# BodyCaINv0_1.net
KiCad netlist of a schematic drawn in Altium Designer
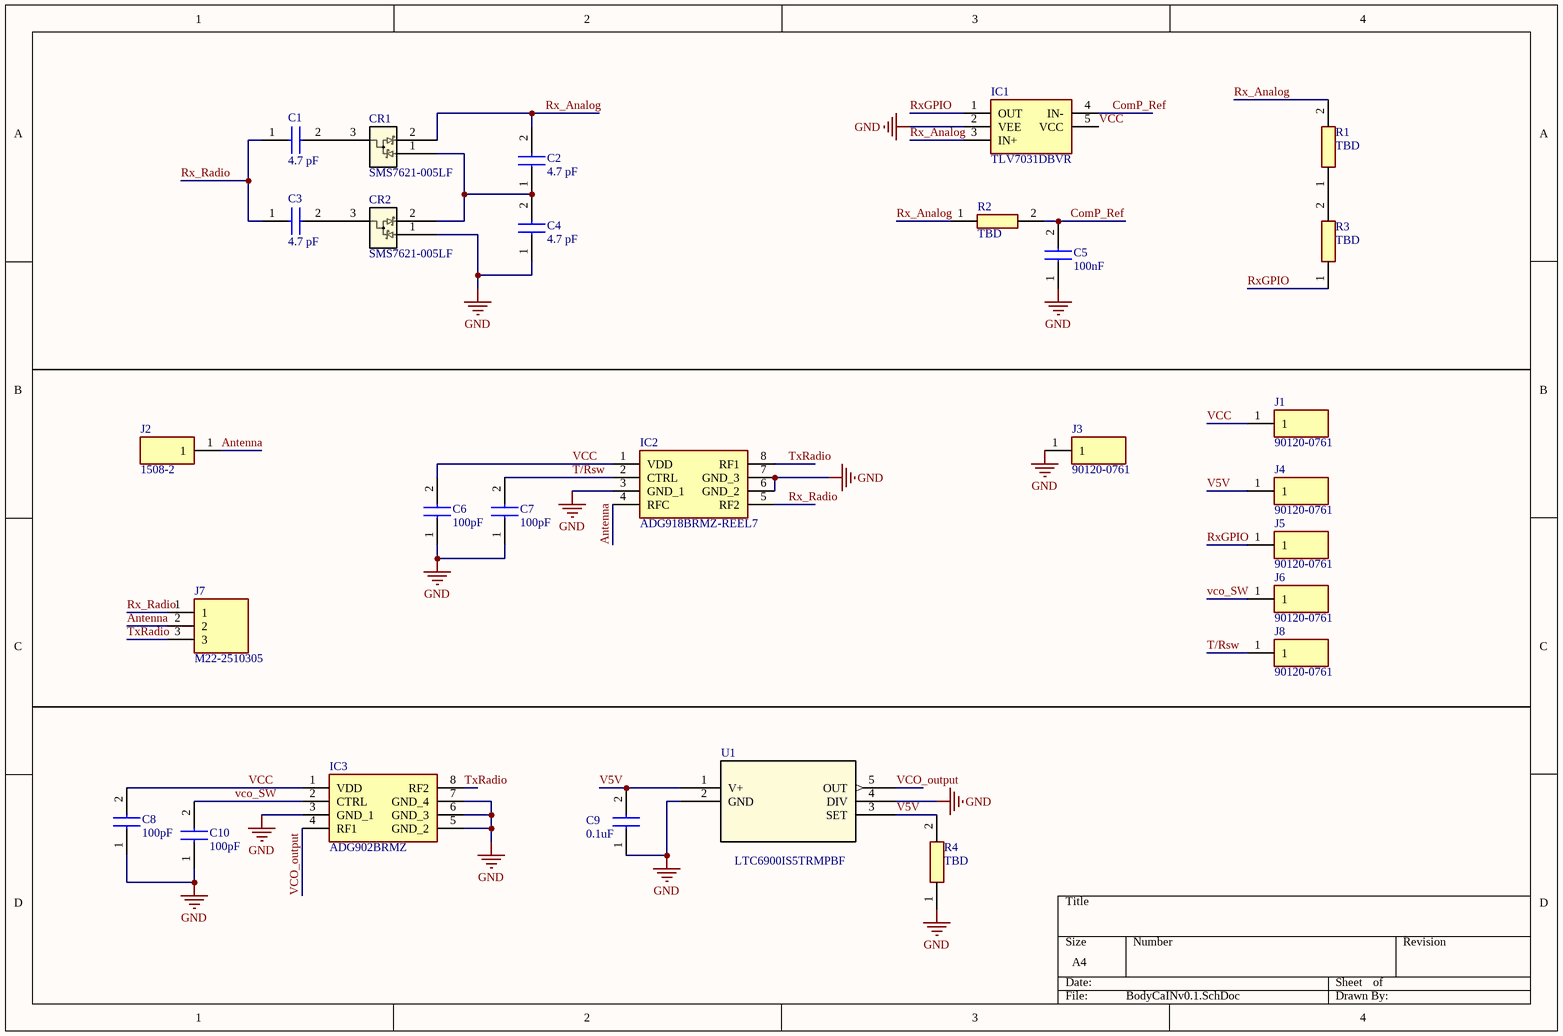
[diagram p0: BodyCaINv0.1.SchDoc]

(export (version "E")
  (design (tool "Eeschema 10.0.6"))
  (components
    (comp (ref "C1")
      (value "4.7 pF")
      (footprint "SamacSys:CAPC1608X73N")
      (description "Capacitor 06035J4R7BBSTR")
      (fields
        (field (name "MANUFACTURER_PART_NUMBER") "06035J4R7BBSTR")
        (field (name "MOUSER PART NUMBER") "581-06035J4R7BBS")
      )
      (libsource (lib "*") (part "06035J4R7BBSTR"))
    )
    (comp (ref "C2")
      (value "4.7 pF")
      (footprint "SamacSys:CAPC1608X73N")
      (description "Capacitor 06035J4R7BBSTR")
      (fields
        (field (name "MANUFACTURER_PART_NUMBER") "06035J4R7BBSTR")
        (field (name "MOUSER PART NUMBER") "581-06035J4R7BBS")
      )
      (libsource (lib "*") (part "06035J4R7BBSTR"))
    )
    (comp (ref "C3")
      (value "4.7 pF")
      (footprint "SamacSys:CAPC1608X73N")
      (description "Capacitor 06035J4R7BBSTR")
      (fields
        (field (name "MANUFACTURER_PART_NUMBER") "06035J4R7BBSTR")
        (field (name "MOUSER PART NUMBER") "581-06035J4R7BBS")
      )
      (libsource (lib "*") (part "06035J4R7BBSTR"))
    )
    (comp (ref "C4")
      (value "4.7 pF")
      (footprint "SamacSys:CAPC1608X73N")
      (description "Capacitor 06035J4R7BBSTR")
      (fields
        (field (name "MANUFACTURER_PART_NUMBER") "06035J4R7BBSTR")
        (field (name "MOUSER PART NUMBER") "581-06035J4R7BBS")
      )
      (libsource (lib "*") (part "06035J4R7BBSTR"))
    )
    (comp (ref "C5")
      (value "100nF")
      (footprint "SamacSys:CAPC1608X90N")
      (description "Capacitor GCM188R71H103KA37J")
      (fields
        (field (name "MANUFACTURER_PART_NUMBER") "GCM188R71H103KA37J")
        (field (name "MOUSER PART NUMBER") "81-GCM188R71H103KA7J")
      )
      (libsource (lib "*") (part "GCM188R71H103KA37J"))
    )
    (comp (ref "C6")
      (value "100pF")
      (footprint "SamacSys:CAPC1608X97N")
      (description "Capacitor VJ0603A101FXAAC")
      (fields
        (field (name "MANUFACTURER_PART_NUMBER") "VJ0603A101FXAAC")
        (field (name "MOUSER PART NUMBER") "77-VJ0603A101FXAAC")
      )
      (libsource (lib "*") (part "VJ0603A101FXAAC"))
    )
    (comp (ref "C7")
      (value "100pF")
      (footprint "SamacSys:CAPC1608X97N")
      (description "Capacitor VJ0603A101FXAAC")
      (fields
        (field (name "MANUFACTURER_PART_NUMBER") "VJ0603A101FXAAC")
        (field (name "MOUSER PART NUMBER") "77-VJ0603A101FXAAC")
      )
      (libsource (lib "*") (part "VJ0603A101FXAAC"))
    )
    (comp (ref "C8")
      (value "100pF")
      (footprint "SamacSys:CAPC1608X97N")
      (description "Capacitor VJ0603A101FXAAC")
      (fields
        (field (name "MANUFACTURER_PART_NUMBER") "VJ0603A101FXAAC")
        (field (name "MOUSER PART NUMBER") "77-VJ0603A101FXAAC")
      )
      (libsource (lib "*") (part "VJ0603A101FXAAC"))
    )
    (comp (ref "C9")
      (value "0.1uF")
      (footprint "SamacSys:CAPC1608X100N")
      (description "CapacitorC0603X104K1RACTU")
      (fields (field (name "MANUFACTURER_PART_NUMBER") "C0603X104K1RACTU"))
      (libsource (lib "*") (part "C0603X104K1RACTU"))
    )
    (comp (ref "C10")
      (value "100pF")
      (footprint "SamacSys:CAPC1608X97N")
      (description "Capacitor VJ0603A101FXAAC")
      (fields
        (field (name "MANUFACTURER_PART_NUMBER") "VJ0603A101FXAAC")
        (field (name "MOUSER PART NUMBER") "77-VJ0603A101FXAAC")
      )
      (libsource (lib "*") (part "VJ0603A101FXAAC"))
    )
    (comp (ref "CR1")
      (value "SMS7621-005LF")
      (footprint "SOT23")
      (description "No Description Available")
      (libsource (lib "SMS7621-005LF") (part "SMS7621-005LF"))
    )
    (comp (ref "CR2")
      (value "SMS7621-005LF")
      (footprint "SOT23")
      (description "No Description Available")
      (libsource (lib "SMS7621-005LF") (part "SMS7621-005LF"))
    )
    (comp (ref "IC1")
      (value "TLV7031DBVR")
      (footprint "SOT95P280X145-5N")
      (description "Integrated Circuit")
      (fields (field (name "MOUSER PART NUMBER") "595-TLV7031DBVR"))
      (libsource (lib "CaINv3.02") (part "TLV7031DBVR"))
    )
    (comp (ref "IC2")
      (value "ADG918BRMZ-REEL7")
      (footprint "SOP65P490X110-8N")
      (description "Integrated Circuit")
      (fields (field (name "MOUSER PART NUMBER") "584-ADG918BRMZ-R7"))
      (libsource (lib "CaINv3.02") (part "ADG918BRMZ-REEL7"))
    )
    (comp (ref "IC3")
      (value "ADG902BRMZ")
      (footprint "SOP65P490X110-8N")
      (description "Integrated Circuit")
      (fields (field (name "MOUSER PART NUMBER") "584-ADG902BRMZ"))
      (libsource (lib "CaINv3.02") (part "ADG902BRMZ"))
    )
    (comp (ref "J1")
      (value "90120-0761")
      (footprint "SamacSys:HDRV1W90P0X254_1X1_232X249X560P")
      (description "Connector")
      (fields (field (name "MOUSER PART NUMBER") "538-90120-0761"))
      (libsource (lib "*") (part "90120-0761"))
    )
    (comp (ref "J2")
      (value "1508-2")
      (footprint "SamacSys:15082")
      (description "Connector")
      (fields (field (name "MOUSER PART NUMBER") "534-1508-2"))
      (libsource (lib "*") (part "1508-2"))
    )
    (comp (ref "J3")
      (value "90120-0761")
      (footprint "SamacSys:HDRV1W90P0X254_1X1_232X249X560P")
      (description "Connector")
      (fields (field (name "MOUSER PART NUMBER") "538-90120-0761"))
      (libsource (lib "*") (part "90120-0761"))
    )
    (comp (ref "J4")
      (value "90120-0761")
      (footprint "SamacSys:HDRV1W90P0X254_1X1_232X249X560P")
      (description "Connector")
      (fields (field (name "MOUSER PART NUMBER") "538-90120-0761"))
      (libsource (lib "*") (part "90120-0761"))
    )
    (comp (ref "J5")
      (value "90120-0761")
      (footprint "SamacSys:HDRV1W90P0X254_1X1_232X249X560P")
      (description "Connector")
      (fields (field (name "MOUSER PART NUMBER") "538-90120-0761"))
      (libsource (lib "*") (part "90120-0761"))
    )
    (comp (ref "J6")
      (value "90120-0761")
      (footprint "SamacSys:HDRV1W90P0X254_1X1_232X249X560P")
      (description "Connector")
      (fields (field (name "MOUSER PART NUMBER") "538-90120-0761"))
      (libsource (lib "*") (part "90120-0761"))
    )
    (comp (ref "J7")
      (value "M22-2510305")
      (footprint "HDRV3W60P0X200_1X3_600X200X525P")
      (description "Connector")
      (fields (field (name "MOUSER PART NUMBER") "855-M22-2510305"))
      (libsource (lib "CaINv3.02") (part "M22-2510305"))
    )
    (comp (ref "J8")
      (value "90120-0761")
      (footprint "SamacSys:HDRV1W90P0X254_1X1_232X249X560P")
      (description "Connector")
      (fields (field (name "MOUSER PART NUMBER") "538-90120-0761"))
      (libsource (lib "*") (part "90120-0761"))
    )
    (comp (ref "R1")
      (value "TBD")
      (footprint "SamacSys:RESC1508X46N")
      (description "Resistor WSL060300000ZEA9")
      (fields
        (field (name "MANUFACTURER_PART_NUMBER") "WSL060300000ZEA9")
        (field (name "MOUSER PART NUMBER") "71-WSL060300000ZEA9")
      )
      (libsource (lib "") (part "WSL060300000ZEA9_1"))
    )
    (comp (ref "R2")
      (value "TBD")
      (footprint "SamacSys:RESC1508X46N")
      (description "Resistor WSL060300000ZEA9")
      (fields
        (field (name "MANUFACTURER_PART_NUMBER") "WSL060300000ZEA9")
        (field (name "MOUSER PART NUMBER") "71-WSL060300000ZEA9")
      )
      (libsource (lib "*") (part "WSL060300000ZEA9"))
    )
    (comp (ref "R3")
      (value "TBD")
      (footprint "SamacSys:RESC1508X46N")
      (description "Resistor WSL060300000ZEA9")
      (fields
        (field (name "MANUFACTURER_PART_NUMBER") "WSL060300000ZEA9")
        (field (name "MOUSER PART NUMBER") "71-WSL060300000ZEA9")
      )
      (libsource (lib "") (part "WSL060300000ZEA9_1"))
    )
    (comp (ref "R4")
      (value "TBD")
      (footprint "SamacSys:RESC1508X46N")
      (description "Resistor WSL060300000ZEA9")
      (fields
        (field (name "MANUFACTURER_PART_NUMBER") "WSL060300000ZEA9")
        (field (name "MOUSER PART NUMBER") "71-WSL060300000ZEA9")
      )
      (libsource (lib "") (part "WSL060300000ZEA9_1"))
    )
    (comp (ref "U1")
      (value "LTC6900IS5TRMPBF")
      (footprint "S_5_ADI")
      (description "No Description Available")
      (libsource (lib "LTC6900IS5TRMPBF") (part "LTC6900IS5TRMPBF"))
    )
  )
  (nets
    (net (code "1") (name "/Antenna") (class "Default")
      (node (ref "IC2") (pin "4") (pinfunction "RFC_4") (pintype "passive"))
      (node (ref "J2") (pin "1") (pinfunction "1_1") (pintype "passive"))
      (node (ref "J7") (pin "2") (pinfunction "2_2") (pintype "passive"))
    )
    (net (code "2") (name "/ComP_Ref") (class "Default")
      (node (ref "C5") (pin "2") (pinfunction "2_2") (pintype "passive"))
      (node (ref "IC1") (pin "4") (pinfunction "IN-_4") (pintype "passive"))
      (node (ref "R2") (pin "2") (pinfunction "2_2") (pintype "passive"))
    )
    (net (code "3") (name "/RxGPIO") (class "Default")
      (node (ref "IC1") (pin "1") (pinfunction "OUT_1") (pintype "passive"))
      (node (ref "J5") (pin "1") (pinfunction "1_1") (pintype "passive"))
      (node (ref "R3") (pin "1") (pinfunction "1_1") (pintype "passive"))
    )
    (net (code "4") (name "/Rx_Analog") (class "Default")
      (node (ref "C2") (pin "2") (pinfunction "2_2") (pintype "passive"))
      (node (ref "CR1") (pin "2") (pinfunction "2_2") (pintype "passive"))
      (node (ref "IC1") (pin "3") (pinfunction "IN+_3") (pintype "passive"))
      (node (ref "R1") (pin "2") (pinfunction "2_2") (pintype "passive"))
      (node (ref "R2") (pin "1") (pinfunction "1_1") (pintype "passive"))
    )
    (net (code "5") (name "/Rx_Radio") (class "Default")
      (node (ref "C1") (pin "1") (pinfunction "1_1") (pintype "passive"))
      (node (ref "C3") (pin "1") (pinfunction "1_1") (pintype "passive"))
      (node (ref "IC2") (pin "5") (pinfunction "RF2_5") (pintype "passive"))
      (node (ref "J7") (pin "1") (pinfunction "1_1") (pintype "passive"))
    )
    (net (code "6") (name "/TxRadio") (class "Default")
      (node (ref "IC2") (pin "8") (pinfunction "RF1_8") (pintype "passive"))
      (node (ref "IC3") (pin "8") (pinfunction "RF2_8") (pintype "passive"))
      (node (ref "J7") (pin "3") (pinfunction "3_3") (pintype "passive"))
    )
    (net (code "7") (name "/T{slash}Rsw") (class "Default")
      (node (ref "C7") (pin "2") (pinfunction "2_2") (pintype "passive"))
      (node (ref "IC2") (pin "2") (pinfunction "CTRL_2") (pintype "passive"))
      (node (ref "J8") (pin "1") (pinfunction "1_1") (pintype "passive"))
    )
    (net (code "8") (name "/V5V") (class "Default")
      (node (ref "C9") (pin "2") (pinfunction "2_2") (pintype "passive"))
      (node (ref "J4") (pin "1") (pinfunction "1_1") (pintype "passive"))
      (node (ref "R4") (pin "2") (pinfunction "2_2") (pintype "passive"))
      (node (ref "U1") (pin "1") (pinfunction "V+_1") (pintype "passive"))
      (node (ref "U1") (pin "3") (pinfunction "SET_3") (pintype "passive"))
    )
    (net (code "9") (name "/VCC") (class "Default")
      (node (ref "C6") (pin "2") (pinfunction "2_2") (pintype "passive"))
      (node (ref "C8") (pin "2") (pinfunction "2_2") (pintype "passive"))
      (node (ref "IC1") (pin "5") (pinfunction "VCC_5") (pintype "passive"))
      (node (ref "IC2") (pin "1") (pinfunction "VDD_1") (pintype "passive"))
      (node (ref "IC3") (pin "1") (pinfunction "VDD_1") (pintype "passive"))
      (node (ref "J1") (pin "1") (pinfunction "1_1") (pintype "passive"))
    )
    (net (code "10") (name "/VCO_output") (class "Default")
      (node (ref "IC3") (pin "4") (pinfunction "RF1_4") (pintype "passive"))
      (node (ref "U1") (pin "5") (pinfunction "OUT_5") (pintype "output"))
    )
    (net (code "11") (name "/vco_SW") (class "Default")
      (node (ref "C10") (pin "2") (pinfunction "2_2") (pintype "passive"))
      (node (ref "IC3") (pin "2") (pinfunction "CTRL_2") (pintype "passive"))
      (node (ref "J6") (pin "1") (pinfunction "1_1") (pintype "passive"))
    )
    (net (code "12") (name "GND") (class "Default")
      (node (ref "C10") (pin "1") (pinfunction "1_1") (pintype "passive"))
      (node (ref "C4") (pin "1") (pinfunction "1_1") (pintype "passive"))
      (node (ref "C5") (pin "1") (pinfunction "1_1") (pintype "passive"))
      (node (ref "C6") (pin "1") (pinfunction "1_1") (pintype "passive"))
      (node (ref "C7") (pin "1") (pinfunction "1_1") (pintype "passive"))
      (node (ref "C8") (pin "1") (pinfunction "1_1") (pintype "passive"))
      (node (ref "C9") (pin "1") (pinfunction "1_1") (pintype "passive"))
      (node (ref "CR2") (pin "1") (pinfunction "1_1") (pintype "passive"))
      (node (ref "IC1") (pin "2") (pinfunction "VEE_2") (pintype "passive"))
      (node (ref "IC2") (pin "3") (pinfunction "GND_1_3") (pintype "passive"))
      (node (ref "IC2") (pin "6") (pinfunction "GND_2_6") (pintype "passive"))
      (node (ref "IC2") (pin "7") (pinfunction "GND_3_7") (pintype "passive"))
      (node (ref "IC3") (pin "3") (pinfunction "GND_1_3") (pintype "passive"))
      (node (ref "IC3") (pin "5") (pinfunction "GND_2_5") (pintype "passive"))
      (node (ref "IC3") (pin "6") (pinfunction "GND_3_6") (pintype "passive"))
      (node (ref "IC3") (pin "7") (pinfunction "GND_4_7") (pintype "passive"))
      (node (ref "J3") (pin "1") (pinfunction "1_1") (pintype "passive"))
      (node (ref "R4") (pin "1") (pinfunction "1_1") (pintype "passive"))
      (node (ref "U1") (pin "2") (pinfunction "GND_2") (pintype "power_in"))
      (node (ref "U1") (pin "4") (pinfunction "DIV_4") (pintype "passive"))
    )
    (net (code "13") (name "Net-(C1-Pad2)") (class "Default")
      (node (ref "C1") (pin "2") (pinfunction "2_2") (pintype "passive"))
      (node (ref "CR1") (pin "3") (pinfunction "3_3") (pintype "passive"))
    )
    (net (code "14") (name "Net-(C2-Pad1)") (class "Default")
      (node (ref "C2") (pin "1") (pinfunction "1_1") (pintype "passive"))
      (node (ref "C4") (pin "2") (pinfunction "2_2") (pintype "passive"))
      (node (ref "CR1") (pin "1") (pinfunction "1_1") (pintype "passive"))
      (node (ref "CR2") (pin "2") (pinfunction "2_2") (pintype "passive"))
    )
    (net (code "15") (name "Net-(C3-Pad2)") (class "Default")
      (node (ref "C3") (pin "2") (pinfunction "2_2") (pintype "passive"))
      (node (ref "CR2") (pin "3") (pinfunction "3_3") (pintype "passive"))
    )
    (net (code "16") (name "Net-(R1-Pad1)") (class "Default")
      (node (ref "R1") (pin "1") (pinfunction "1_1") (pintype "passive"))
      (node (ref "R3") (pin "2") (pinfunction "2_2") (pintype "passive"))
    )
  )
)
